# Simple-Bug-2N918.net
KiCad netlist of a schematic drawn in EAGLE
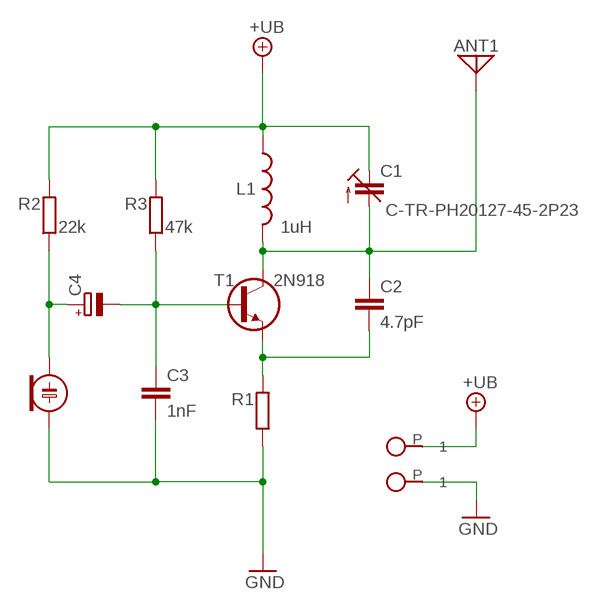
[diagram p0: schematic, sheet 1]

(export (version "E")
  (design (tool "Eeschema 10.0.6"))
  (components
    (comp (ref "+")
      (value "SPAD")
      (footprint "eagle-import:SPAD")
      (libsource (lib "eagle-import") (part "SPAD"))
    )
    (comp (ref "ANT1")
      (value "ANT")
      (footprint "eagle-import:SPAD")
      (libsource (lib "eagle-import") (part "ANT"))
    )
    (comp (ref "C1")
      (value "C-TR-PH20127-45-2P23")
      (footprint "eagle-import:TRIM808-45")
      (libsource (lib "eagle-import") (part "C-TR-PH20127-45-2P23"))
    )
    (comp (ref "C2")
      (value "4.7pF")
      (footprint "eagle-import:C025-020X036")
      (libsource (lib "eagle-import") (part "C025-020X036"))
    )
    (comp (ref "C3")
      (value "1nF")
      (footprint "eagle-import:C025-020X036")
      (libsource (lib "eagle-import") (part "C025-020X036"))
    )
    (comp (ref "C4")
      (value "CPOLE2,5-3")
      (footprint "eagle-import:E2,5-3")
      (libsource (lib "eagle-import") (part "CPOLE2,5-3"))
    )
    (comp (ref "ECM")
      (value "ECM-5")
      (footprint "eagle-import:ECM-5")
      (libsource (lib "eagle-import") (part "ECM-5"))
    )
    (comp (ref "L1")
      (value "1uH")
      (footprint "eagle-import:L-04_7")
      (libsource (lib "eagle-import") (part "L04/7"))
    )
    (comp (ref "R1")
      (value "R0202V")
      (footprint "eagle-import:0202V")
      (libsource (lib "eagle-import") (part "R0202V"))
    )
    (comp (ref "R2")
      (value "22k")
      (footprint "eagle-import:0202_5")
      (libsource (lib "eagle-import") (part "R0202/5"))
    )
    (comp (ref "R3")
      (value "47k")
      (footprint "eagle-import:0202_5")
      (libsource (lib "eagle-import") (part "R0202/5"))
    )
    (comp (ref "T1")
      (value "2N918")
      (footprint "eagle-import:TO-72-A45")
      (libsource (lib "eagle-import") (part "2N918TO-72-A45"))
    )
    (comp (ref "̶̶")
      (value "SPAD")
      (footprint "eagle-import:SPAD")
      (libsource (lib "eagle-import") (part "SPAD"))
    )
  )
  (nets
    (net (code "1") (name "+UB") (class "Default")
      (node (ref "+") (pin "P") (pinfunction "1_P") (pintype "bidirectional"))
      (node (ref "C1") (pin "3") (pinfunction "E_3") (pintype "passive"))
      (node (ref "L1") (pin "1") (pinfunction "1_1") (pintype "passive"))
      (node (ref "R2") (pin "2") (pinfunction "2_2") (pintype "passive"))
      (node (ref "R3") (pin "2") (pinfunction "2_2") (pintype "passive"))
    )
    (net (code "2") (name "GND") (class "Default")
      (node (ref "C3") (pin "2") (pinfunction "2_2") (pintype "passive"))
      (node (ref "ECM") (pin "1") (pinfunction "+_1") (pintype "passive"))
      (node (ref "R1") (pin "1") (pinfunction "1_1") (pintype "passive"))
      (node (ref "̶̶") (pin "P") (pinfunction "1_P") (pintype "bidirectional"))
    )
    (net (code "3") (name "Net-(ANT1-1)") (class "Default")
      (node (ref "ANT1") (pin "P") (pinfunction "1_P") (pintype "output"))
      (node (ref "C1") (pin "2") (pinfunction "A_2") (pintype "passive"))
      (node (ref "C2") (pin "1") (pinfunction "1_1") (pintype "passive"))
      (node (ref "L1") (pin "2") (pinfunction "2_2") (pintype "passive"))
      (node (ref "T1") (pin "3") (pinfunction "C_3") (pintype "passive"))
    )
    (net (code "4") (name "Net-(ECM--)") (class "Default")
      (node (ref "C4") (pin "+") (pinfunction "+_+") (pintype "passive"))
      (node (ref "ECM") (pin "2") (pinfunction "-_2") (pintype "passive"))
      (node (ref "R2") (pin "1") (pinfunction "1_1") (pintype "passive"))
    )
    (net (code "5") (name "Net-(T1-B)") (class "Default")
      (node (ref "C3") (pin "1") (pinfunction "1_1") (pintype "passive"))
      (node (ref "C4") (pin "-") (pinfunction "-_-") (pintype "passive"))
      (node (ref "R3") (pin "1") (pinfunction "1_1") (pintype "passive"))
      (node (ref "T1") (pin "2") (pinfunction "B_2") (pintype "passive"))
    )
    (net (code "6") (name "Net-(T1-E)") (class "Default")
      (node (ref "C2") (pin "2") (pinfunction "2_2") (pintype "passive"))
      (node (ref "R1") (pin "2") (pinfunction "2_2") (pintype "passive"))
      (node (ref "T1") (pin "1") (pinfunction "E_1") (pintype "passive"))
    )
  )
)
